# eps_bt1.net
KiCad netlist of a schematic drawn in Altium Designer
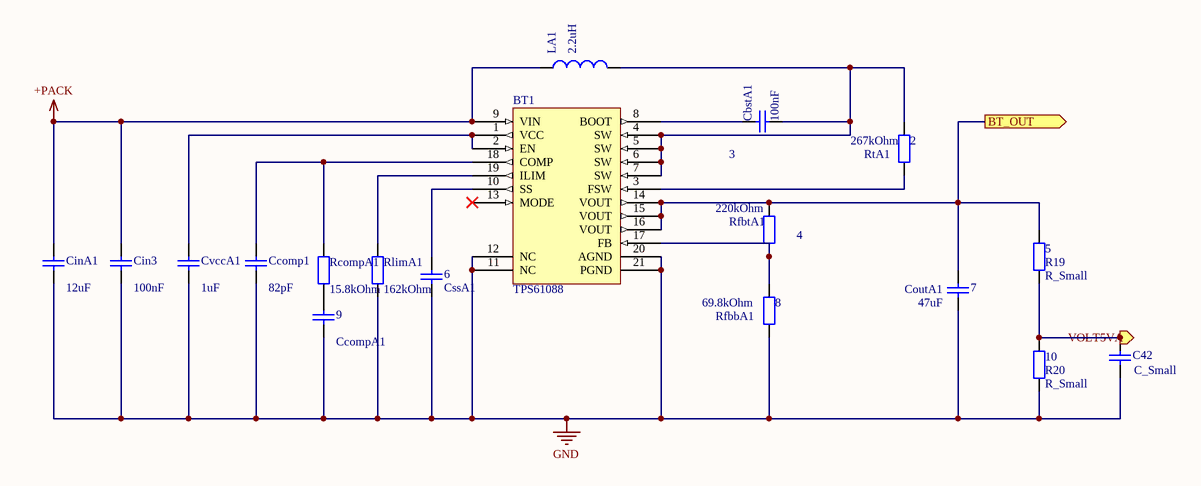
[diagram p0: eps_bt1.SchDoc]

(export (version "E")
  (design (tool "Eeschema 10.0.6"))
  (components
    (comp (ref "2")
      (value "RtA1")
      (footprint "1608[0603]")
      (description "Resistor")
      (fields (field (name "ALTIUM_VALUE") "267kOhm") (field (name "PUBLISHER") "Altium Limited"))
      (libsource (lib "Miscellaneous Devices") (part "Res2"))
    )
    (comp (ref "3")
      (value "CbstA1")
      (footprint "1608[0603]")
      (description "Capacitor")
      (fields (field (name "ALTIUM_VALUE") "100nF") (field (name "PUBLISHER") "Altium Limited"))
      (libsource (lib "Miscellaneous Devices") (part "Cap"))
    )
    (comp (ref "4")
      (value "RfbtA1")
      (footprint "1608[0603]")
      (description "Resistor")
      (fields (field (name "ALTIUM_VALUE") "220kOhm") (field (name "PUBLISHER") "Altium Limited"))
      (libsource (lib "") (part "Res2_1"))
    )
    (comp (ref "5")
      (value "R19")
      (footprint "1608[0603]")
      (description "Resistor")
      (fields (field (name "ALTIUM_VALUE") "R_Small") (field (name "PUBLISHER") "Altium Limited"))
      (libsource (lib "") (part "Res2_1"))
    )
    (comp (ref "6")
      (value "CssA1")
      (footprint "1608[0603]")
      (description "Capacitor")
      (fields (field (name "PUBLISHER") "Altium Limited"))
      (libsource (lib "Miscellaneous Devices") (part "Cap"))
    )
    (comp (ref "7")
      (value "CoutA1")
      (footprint "1608[0603]")
      (description "Capacitor")
      (fields (field (name "ALTIUM_VALUE") "47uF") (field (name "PUBLISHER") "Altium Limited"))
      (libsource (lib "Miscellaneous Devices") (part "Cap"))
    )
    (comp (ref "8")
      (value "RfbbA1")
      (footprint "1608[0603]")
      (description "Resistor")
      (fields (field (name "ALTIUM_VALUE") "69.8kOhm") (field (name "PUBLISHER") "Altium Limited"))
      (libsource (lib "") (part "Res2_1"))
    )
    (comp (ref "9")
      (value "CcompA1")
      (footprint "1608[0603]")
      (description "Capacitor")
      (fields (field (name "PUBLISHER") "Altium Limited"))
      (libsource (lib "Miscellaneous Devices") (part "Cap"))
    )
    (comp (ref "10")
      (value "R20")
      (footprint "1608[0603]")
      (description "Resistor")
      (fields (field (name "ALTIUM_VALUE") "R_Small") (field (name "PUBLISHER") "Altium Limited"))
      (libsource (lib "") (part "Res2_1"))
    )
    (comp (ref "BT1")
      (value "TPS61088")
      (footprint "QFN50P450X350X100-21N")
      (description "Boost converter")
      (libsource (lib "heron-general") (part "TPS61088"))
    )
    (comp (ref "C42")
      (value "C_Small")
      (footprint "1608[0603]")
      (description "Capacitor")
      (fields (field (name "PUBLISHER") "Altium Limited"))
      (libsource (lib "Miscellaneous Devices") (part "Cap"))
    )
    (comp (ref "Ccomp1")
      (value "82pF")
      (footprint "1608[0603]")
      (description "Capacitor")
      (fields (field (name "PUBLISHER") "Altium Limited"))
      (libsource (lib "Miscellaneous Devices") (part "Cap"))
    )
    (comp (ref "Cin3")
      (value "100nF")
      (footprint "1608[0603]")
      (description "Capacitor")
      (fields (field (name "PUBLISHER") "Altium Limited"))
      (libsource (lib "Miscellaneous Devices") (part "Cap"))
    )
    (comp (ref "CinA1")
      (value "12uF")
      (footprint "1608[0603]")
      (description "Capacitor")
      (fields (field (name "PUBLISHER") "Altium Limited"))
      (libsource (lib "Miscellaneous Devices") (part "Cap"))
    )
    (comp (ref "CvccA1")
      (value "1uF")
      (footprint "1608[0603]")
      (description "Capacitor")
      (fields (field (name "PUBLISHER") "Altium Limited"))
      (libsource (lib "Miscellaneous Devices") (part "Cap"))
    )
    (comp (ref "LA1")
      (value "2.2uH")
      (footprint "1608[0603]")
      (description "Inductor")
      (fields (field (name "PUBLISHER") "Altium Limited"))
      (libsource (lib "Miscellaneous Devices") (part "Inductor"))
    )
    (comp (ref "RcompA1")
      (value "15.8kOhm")
      (footprint "1608[0603]")
      (description "Resistor")
      (fields (field (name "PUBLISHER") "Altium Limited"))
      (libsource (lib "") (part "Res2_1"))
    )
    (comp (ref "RlimA1")
      (value "162kOhm")
      (footprint "1608[0603]")
      (description "Resistor")
      (fields (field (name "PUBLISHER") "Altium Limited"))
      (libsource (lib "") (part "Res2_1"))
    )
  )
  (nets
    (net (code "1") (name "+PACK") (class "Default")
      (node (ref "BT1") (pin "9") (pinfunction "VIN_9") (pintype "input"))
      (node (ref "Cin3") (pin "2") (pinfunction "2_2") (pintype "passive"))
      (node (ref "CinA1") (pin "2") (pinfunction "2_2") (pintype "passive"))
      (node (ref "LA1") (pin "1") (pinfunction "1_1") (pintype "passive"))
    )
    (net (code "2") (name "/BT_OUT") (class "Default")
      (node (ref "4") (pin "2") (pinfunction "2_2") (pintype "passive"))
      (node (ref "5") (pin "2") (pinfunction "2_2") (pintype "passive"))
      (node (ref "7") (pin "2") (pinfunction "2_2") (pintype "passive"))
      (node (ref "BT1") (pin "14") (pinfunction "VOUT_14") (pintype "output"))
      (node (ref "BT1") (pin "15") (pinfunction "VOUT_15") (pintype "output"))
      (node (ref "BT1") (pin "16") (pinfunction "VOUT_16") (pintype "output"))
    )
    (net (code "3") (name "/VOLT5VA") (class "Default")
      (node (ref "10") (pin "2") (pinfunction "2_2") (pintype "passive"))
      (node (ref "5") (pin "1") (pinfunction "1_1") (pintype "passive"))
      (node (ref "C42") (pin "1") (pinfunction "1_1") (pintype "passive"))
    )
    (net (code "4") (name "GND") (class "Default")
      (node (ref "10") (pin "1") (pinfunction "1_1") (pintype "passive"))
      (node (ref "6") (pin "1") (pinfunction "1_1") (pintype "passive"))
      (node (ref "7") (pin "1") (pinfunction "1_1") (pintype "passive"))
      (node (ref "8") (pin "1") (pinfunction "1_1") (pintype "passive"))
      (node (ref "9") (pin "1") (pinfunction "1_1") (pintype "passive"))
      (node (ref "BT1") (pin "11") (pinfunction "NC_11") (pintype "passive"))
      (node (ref "BT1") (pin "12") (pinfunction "NC_12") (pintype "passive"))
      (node (ref "BT1") (pin "20") (pinfunction "AGND_20") (pintype "power_in"))
      (node (ref "BT1") (pin "21") (pinfunction "PGND_21") (pintype "power_in"))
      (node (ref "C42") (pin "2") (pinfunction "2_2") (pintype "passive"))
      (node (ref "Ccomp1") (pin "1") (pinfunction "1_1") (pintype "passive"))
      (node (ref "Cin3") (pin "1") (pinfunction "1_1") (pintype "passive"))
      (node (ref "CinA1") (pin "1") (pinfunction "1_1") (pintype "passive"))
      (node (ref "CvccA1") (pin "1") (pinfunction "1_1") (pintype "passive"))
      (node (ref "RlimA1") (pin "1") (pinfunction "1_1") (pintype "passive"))
    )
    (net (code "5") (name "Net-(2-Pad1)") (class "Default")
      (node (ref "2") (pin "1") (pinfunction "1_1") (pintype "passive"))
      (node (ref "3") (pin "1") (pinfunction "1_1") (pintype "passive"))
      (node (ref "BT1") (pin "4") (pinfunction "SW_4") (pintype "input"))
      (node (ref "BT1") (pin "5") (pinfunction "SW_5") (pintype "input"))
      (node (ref "BT1") (pin "6") (pinfunction "SW_6") (pintype "input"))
      (node (ref "BT1") (pin "7") (pinfunction "SW_7") (pintype "input"))
      (node (ref "LA1") (pin "2") (pinfunction "2_2") (pintype "passive"))
    )
    (net (code "6") (name "Net-(9-Pad2)") (class "Default")
      (node (ref "9") (pin "2") (pinfunction "2_2") (pintype "passive"))
      (node (ref "RcompA1") (pin "1") (pinfunction "1_1") (pintype "passive"))
    )
    (net (code "7") (name "Net-(BT1-BOOT)") (class "Default")
      (node (ref "3") (pin "2") (pinfunction "2_2") (pintype "passive"))
      (node (ref "BT1") (pin "8") (pinfunction "BOOT_8") (pintype "output"))
    )
    (net (code "8") (name "Net-(BT1-COMP)") (class "Default")
      (node (ref "BT1") (pin "18") (pinfunction "COMP_18") (pintype "output"))
      (node (ref "Ccomp1") (pin "2") (pinfunction "2_2") (pintype "passive"))
      (node (ref "RcompA1") (pin "2") (pinfunction "2_2") (pintype "passive"))
    )
    (net (code "9") (name "Net-(BT1-EN)") (class "Default")
      (node (ref "BT1") (pin "1") (pinfunction "VCC_1") (pintype "output"))
      (node (ref "BT1") (pin "2") (pinfunction "EN_2") (pintype "input"))
      (node (ref "CvccA1") (pin "2") (pinfunction "2_2") (pintype "passive"))
    )
    (net (code "10") (name "Net-(BT1-FB)") (class "Default")
      (node (ref "4") (pin "1") (pinfunction "1_1") (pintype "passive"))
      (node (ref "8") (pin "2") (pinfunction "2_2") (pintype "passive"))
      (node (ref "BT1") (pin "17") (pinfunction "FB_17") (pintype "input"))
    )
    (net (code "11") (name "Net-(BT1-FSW)") (class "Default")
      (node (ref "2") (pin "2") (pinfunction "2_2") (pintype "passive"))
      (node (ref "BT1") (pin "3") (pinfunction "FSW_3") (pintype "input"))
    )
    (net (code "12") (name "Net-(BT1-ILIM)") (class "Default")
      (node (ref "BT1") (pin "19") (pinfunction "ILIM_19") (pintype "output"))
      (node (ref "RlimA1") (pin "2") (pinfunction "2_2") (pintype "passive"))
    )
    (net (code "13") (name "Net-(BT1-SS)") (class "Default")
      (node (ref "6") (pin "2") (pinfunction "2_2") (pintype "passive"))
      (node (ref "BT1") (pin "10") (pinfunction "SS_10") (pintype "output"))
    )
    (net (code "14") (name "unconnected-(BT1-MODE-Pad13)") (class "Default")
      (node (ref "BT1") (pin "13") (pinfunction "MODE_13") (pintype "input+no_connect"))
    )
  )
)
